# 06_-_MEMORY.net
KiCad netlist of a schematic drawn in Altium Designer
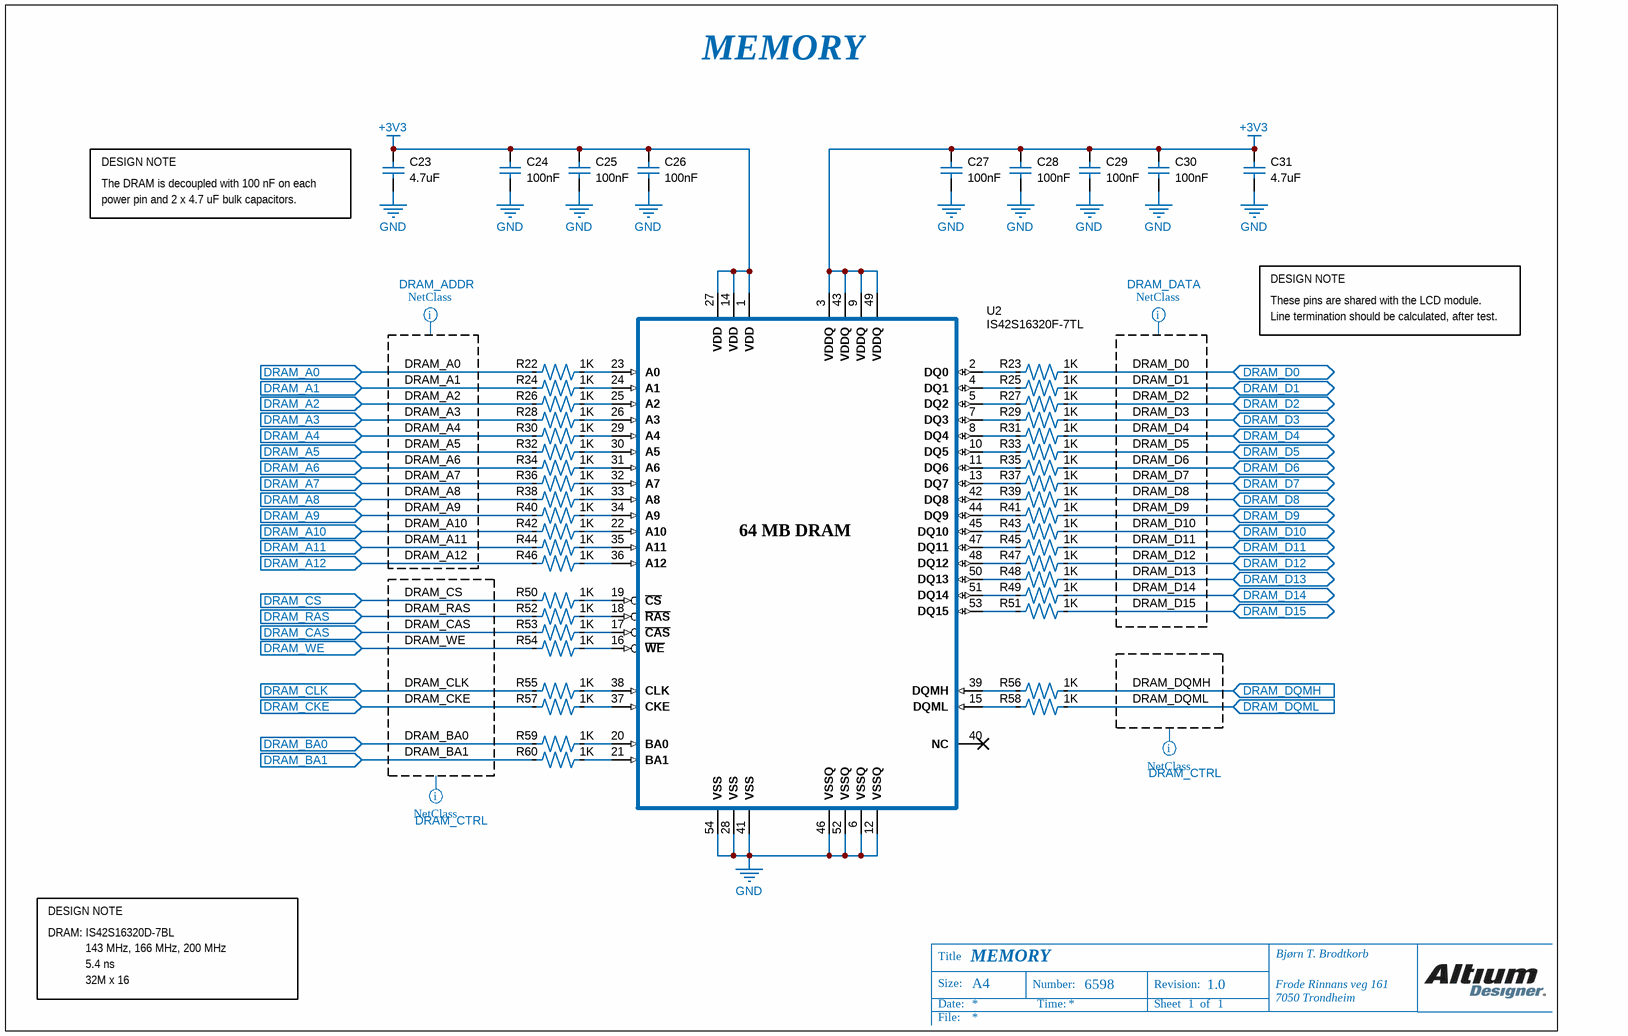
[diagram p0: [06] - MEMORY.SchDoc]

(export (version "E")
  (design (tool "Eeschema 10.0.6"))
  (components
    (comp (ref "C23")
      (value "4.7uF")
      (footprint "C0603")
      (description "C0603")
      (fields (field (name "Comment") "02016D104KAT2A"))
      (libsource (lib "Passive components") (part "02016D104KAT2A"))
    )
    (comp (ref "C24")
      (value "100nF")
      (footprint "C0402")
      (description "C0402")
      (fields (field (name "Comment") "04023C103KAT2A"))
      (libsource (lib "Passive components") (part "04023C103KAT2A"))
    )
    (comp (ref "C25")
      (value "100nF")
      (footprint "C0402")
      (description "C0402")
      (fields (field (name "Comment") "04023C103KAT2A"))
      (libsource (lib "Passive components") (part "04023C103KAT2A"))
    )
    (comp (ref "C26")
      (value "100nF")
      (footprint "C0402")
      (description "C0402")
      (fields (field (name "Comment") "04023C103KAT2A"))
      (libsource (lib "Passive components") (part "04023C103KAT2A"))
    )
    (comp (ref "C27")
      (value "100nF")
      (footprint "C0402")
      (description "C0402")
      (fields (field (name "Comment") "04023C103KAT2A"))
      (libsource (lib "Passive components") (part "04023C103KAT2A"))
    )
    (comp (ref "C28")
      (value "100nF")
      (footprint "C0402")
      (description "C0402")
      (fields (field (name "Comment") "04023C103KAT2A"))
      (libsource (lib "Passive components") (part "04023C103KAT2A"))
    )
    (comp (ref "C29")
      (value "100nF")
      (footprint "C0402")
      (description "C0402")
      (fields (field (name "Comment") "04023C103KAT2A"))
      (libsource (lib "Passive components") (part "04023C103KAT2A"))
    )
    (comp (ref "C30")
      (value "100nF")
      (footprint "C0402")
      (description "C0402")
      (fields (field (name "Comment") "04023C103KAT2A"))
      (libsource (lib "Passive components") (part "04023C103KAT2A"))
    )
    (comp (ref "C31")
      (value "4.7uF")
      (footprint "C0603")
      (description "C0603")
      (fields (field (name "Comment") "02016D104KAT2A"))
      (libsource (lib "Passive components") (part "02016D104KAT2A"))
    )
    (comp (ref "R22")
      (value "1K")
      (footprint "R0402")
      (description "R0402")
      (fields (field (name "Comment") "CRCW04020000Z0ED"))
      (libsource (lib "Passive components") (part "CRCW04020000Z0ED"))
    )
    (comp (ref "R23")
      (value "1K")
      (footprint "R0402")
      (description "R0402")
      (fields (field (name "Comment") "CRCW04020000Z0ED"))
      (libsource (lib "Passive components") (part "CRCW04020000Z0ED"))
    )
    (comp (ref "R24")
      (value "1K")
      (footprint "R0402")
      (description "R0402")
      (fields (field (name "Comment") "CRCW04020000Z0ED"))
      (libsource (lib "Passive components") (part "CRCW04020000Z0ED"))
    )
    (comp (ref "R25")
      (value "1K")
      (footprint "R0402")
      (description "R0402")
      (fields (field (name "Comment") "CRCW04020000Z0ED"))
      (libsource (lib "Passive components") (part "CRCW04020000Z0ED"))
    )
    (comp (ref "R26")
      (value "1K")
      (footprint "R0402")
      (description "R0402")
      (fields (field (name "Comment") "CRCW04020000Z0ED"))
      (libsource (lib "Passive components") (part "CRCW04020000Z0ED"))
    )
    (comp (ref "R27")
      (value "1K")
      (footprint "R0402")
      (description "R0402")
      (fields (field (name "Comment") "CRCW04020000Z0ED"))
      (libsource (lib "Passive components") (part "CRCW04020000Z0ED"))
    )
    (comp (ref "R28")
      (value "1K")
      (footprint "R0402")
      (description "R0402")
      (fields (field (name "Comment") "CRCW04020000Z0ED"))
      (libsource (lib "Passive components") (part "CRCW04020000Z0ED"))
    )
    (comp (ref "R29")
      (value "1K")
      (footprint "R0402")
      (description "R0402")
      (fields (field (name "Comment") "CRCW04020000Z0ED"))
      (libsource (lib "Passive components") (part "CRCW04020000Z0ED"))
    )
    (comp (ref "R30")
      (value "1K")
      (footprint "R0402")
      (description "R0402")
      (fields (field (name "Comment") "CRCW04020000Z0ED"))
      (libsource (lib "Passive components") (part "CRCW04020000Z0ED"))
    )
    (comp (ref "R31")
      (value "1K")
      (footprint "R0402")
      (description "R0402")
      (fields (field (name "Comment") "CRCW04020000Z0ED"))
      (libsource (lib "Passive components") (part "CRCW04020000Z0ED"))
    )
    (comp (ref "R32")
      (value "1K")
      (footprint "R0402")
      (description "R0402")
      (fields (field (name "Comment") "CRCW04020000Z0ED"))
      (libsource (lib "Passive components") (part "CRCW04020000Z0ED"))
    )
    (comp (ref "R33")
      (value "1K")
      (footprint "R0402")
      (description "R0402")
      (fields (field (name "Comment") "CRCW04020000Z0ED"))
      (libsource (lib "Passive components") (part "CRCW04020000Z0ED"))
    )
    (comp (ref "R34")
      (value "1K")
      (footprint "R0402")
      (description "R0402")
      (fields (field (name "Comment") "CRCW04020000Z0ED"))
      (libsource (lib "Passive components") (part "CRCW04020000Z0ED"))
    )
    (comp (ref "R35")
      (value "1K")
      (footprint "R0402")
      (description "R0402")
      (fields (field (name "Comment") "CRCW04020000Z0ED"))
      (libsource (lib "Passive components") (part "CRCW04020000Z0ED"))
    )
    (comp (ref "R36")
      (value "1K")
      (footprint "R0402")
      (description "R0402")
      (fields (field (name "Comment") "CRCW04020000Z0ED"))
      (libsource (lib "Passive components") (part "CRCW04020000Z0ED"))
    )
    (comp (ref "R37")
      (value "1K")
      (footprint "R0402")
      (description "R0402")
      (fields (field (name "Comment") "CRCW04020000Z0ED"))
      (libsource (lib "Passive components") (part "CRCW04020000Z0ED"))
    )
    (comp (ref "R38")
      (value "1K")
      (footprint "R0402")
      (description "R0402")
      (fields (field (name "Comment") "CRCW04020000Z0ED"))
      (libsource (lib "Passive components") (part "CRCW04020000Z0ED"))
    )
    (comp (ref "R39")
      (value "1K")
      (footprint "R0402")
      (description "R0402")
      (fields (field (name "Comment") "CRCW04020000Z0ED"))
      (libsource (lib "Passive components") (part "CRCW04020000Z0ED"))
    )
    (comp (ref "R40")
      (value "1K")
      (footprint "R0402")
      (description "R0402")
      (fields (field (name "Comment") "CRCW04020000Z0ED"))
      (libsource (lib "Passive components") (part "CRCW04020000Z0ED"))
    )
    (comp (ref "R41")
      (value "1K")
      (footprint "R0402")
      (description "R0402")
      (fields (field (name "Comment") "CRCW04020000Z0ED"))
      (libsource (lib "Passive components") (part "CRCW04020000Z0ED"))
    )
    (comp (ref "R42")
      (value "1K")
      (footprint "R0402")
      (description "R0402")
      (fields (field (name "Comment") "CRCW04020000Z0ED"))
      (libsource (lib "Passive components") (part "CRCW04020000Z0ED"))
    )
    (comp (ref "R43")
      (value "1K")
      (footprint "R0402")
      (description "R0402")
      (fields (field (name "Comment") "CRCW04020000Z0ED"))
      (libsource (lib "Passive components") (part "CRCW04020000Z0ED"))
    )
    (comp (ref "R44")
      (value "1K")
      (footprint "R0402")
      (description "R0402")
      (fields (field (name "Comment") "CRCW04020000Z0ED"))
      (libsource (lib "Passive components") (part "CRCW04020000Z0ED"))
    )
    (comp (ref "R45")
      (value "1K")
      (footprint "R0402")
      (description "R0402")
      (fields (field (name "Comment") "CRCW04020000Z0ED"))
      (libsource (lib "Passive components") (part "CRCW04020000Z0ED"))
    )
    (comp (ref "R46")
      (value "1K")
      (footprint "R0402")
      (description "R0402")
      (fields (field (name "Comment") "CRCW04020000Z0ED"))
      (libsource (lib "Passive components") (part "CRCW04020000Z0ED"))
    )
    (comp (ref "R47")
      (value "1K")
      (footprint "R0402")
      (description "R0402")
      (fields (field (name "Comment") "CRCW04020000Z0ED"))
      (libsource (lib "Passive components") (part "CRCW04020000Z0ED"))
    )
    (comp (ref "R48")
      (value "1K")
      (footprint "R0402")
      (description "R0402")
      (fields (field (name "Comment") "CRCW04020000Z0ED"))
      (libsource (lib "Passive components") (part "CRCW04020000Z0ED"))
    )
    (comp (ref "R49")
      (value "1K")
      (footprint "R0402")
      (description "R0402")
      (fields (field (name "Comment") "CRCW04020000Z0ED"))
      (libsource (lib "Passive components") (part "CRCW04020000Z0ED"))
    )
    (comp (ref "R50")
      (value "1K")
      (footprint "R0402")
      (description "R0402")
      (fields (field (name "Comment") "CRCW04020000Z0ED"))
      (libsource (lib "Passive components") (part "CRCW04020000Z0ED"))
    )
    (comp (ref "R51")
      (value "1K")
      (footprint "R0402")
      (description "R0402")
      (fields (field (name "Comment") "CRCW04020000Z0ED"))
      (libsource (lib "Passive components") (part "CRCW04020000Z0ED"))
    )
    (comp (ref "R52")
      (value "1K")
      (footprint "R0402")
      (description "R0402")
      (fields (field (name "Comment") "CRCW04020000Z0ED"))
      (libsource (lib "Passive components") (part "CRCW04020000Z0ED"))
    )
    (comp (ref "R53")
      (value "1K")
      (footprint "R0402")
      (description "R0402")
      (fields (field (name "Comment") "CRCW04020000Z0ED"))
      (libsource (lib "Passive components") (part "CRCW04020000Z0ED"))
    )
    (comp (ref "R54")
      (value "1K")
      (footprint "R0402")
      (description "R0402")
      (fields (field (name "Comment") "CRCW04020000Z0ED"))
      (libsource (lib "Passive components") (part "CRCW04020000Z0ED"))
    )
    (comp (ref "R55")
      (value "1K")
      (footprint "R0402")
      (description "R0402")
      (fields (field (name "Comment") "CRCW04020000Z0ED"))
      (libsource (lib "Passive components") (part "CRCW04020000Z0ED"))
    )
    (comp (ref "R56")
      (value "1K")
      (footprint "R0402")
      (description "R0402")
      (fields (field (name "Comment") "CRCW04020000Z0ED"))
      (libsource (lib "Passive components") (part "CRCW04020000Z0ED"))
    )
    (comp (ref "R57")
      (value "1K")
      (footprint "R0402")
      (description "R0402")
      (fields (field (name "Comment") "CRCW04020000Z0ED"))
      (libsource (lib "Passive components") (part "CRCW04020000Z0ED"))
    )
    (comp (ref "R58")
      (value "1K")
      (footprint "R0402")
      (description "R0402")
      (fields (field (name "Comment") "CRCW04020000Z0ED"))
      (libsource (lib "Passive components") (part "CRCW04020000Z0ED"))
    )
    (comp (ref "R59")
      (value "1K")
      (footprint "R0402")
      (description "R0402")
      (fields (field (name "Comment") "CRCW04020000Z0ED"))
      (libsource (lib "Passive components") (part "CRCW04020000Z0ED"))
    )
    (comp (ref "R60")
      (value "1K")
      (footprint "R0402")
      (description "R0402")
      (fields (field (name "Comment") "CRCW04020000Z0ED"))
      (libsource (lib "Passive components") (part "CRCW04020000Z0ED"))
    )
    (comp (ref "U2")
      (value "IS42S16320F-7TL")
      (footprint "IS42S16320F-7TL")
      (description "SDRAM 512Mb 32Mx16 TSOP")
      (libsource (lib "Memory") (part "IS42S16320F-7TL"))
    )
  )
  (nets
    (net (code "1") (name "+3V3") (class "Default")
      (node (ref "C23") (pin "2") (pinfunction "2_2") (pintype "passive"))
      (node (ref "C24") (pin "2") (pinfunction "2_2") (pintype "passive"))
      (node (ref "C25") (pin "2") (pinfunction "2_2") (pintype "passive"))
      (node (ref "C26") (pin "2") (pinfunction "2_2") (pintype "passive"))
      (node (ref "C27") (pin "2") (pinfunction "2_2") (pintype "passive"))
      (node (ref "C28") (pin "2") (pinfunction "2_2") (pintype "passive"))
      (node (ref "C29") (pin "2") (pinfunction "2_2") (pintype "passive"))
      (node (ref "C30") (pin "2") (pinfunction "2_2") (pintype "passive"))
      (node (ref "C31") (pin "2") (pinfunction "2_2") (pintype "passive"))
      (node (ref "U2") (pin "1") (pinfunction "VDD_1") (pintype "power_in"))
      (node (ref "U2") (pin "14") (pinfunction "VDD_14") (pintype "power_in"))
      (node (ref "U2") (pin "27") (pinfunction "VDD_27") (pintype "power_in"))
      (node (ref "U2") (pin "3") (pinfunction "VDDQ_3") (pintype "power_in"))
      (node (ref "U2") (pin "43") (pinfunction "VDDQ_43") (pintype "power_in"))
      (node (ref "U2") (pin "49") (pinfunction "VDDQ_49") (pintype "power_in"))
      (node (ref "U2") (pin "9") (pinfunction "VDDQ_9") (pintype "power_in"))
    )
    (net (code "2") (name "/DRAM_A0") (class "Default")
      (node (ref "R22") (pin "1") (pinfunction "1_1") (pintype "passive"))
    )
    (net (code "3") (name "/DRAM_A1") (class "Default")
      (node (ref "R24") (pin "1") (pinfunction "1_1") (pintype "passive"))
    )
    (net (code "4") (name "/DRAM_A2") (class "Default")
      (node (ref "R26") (pin "1") (pinfunction "1_1") (pintype "passive"))
    )
    (net (code "5") (name "/DRAM_A3") (class "Default")
      (node (ref "R28") (pin "1") (pinfunction "1_1") (pintype "passive"))
    )
    (net (code "6") (name "/DRAM_A4") (class "Default")
      (node (ref "R30") (pin "1") (pinfunction "1_1") (pintype "passive"))
    )
    (net (code "7") (name "/DRAM_A5") (class "Default")
      (node (ref "R32") (pin "1") (pinfunction "1_1") (pintype "passive"))
    )
    (net (code "8") (name "/DRAM_A6") (class "Default")
      (node (ref "R34") (pin "1") (pinfunction "1_1") (pintype "passive"))
    )
    (net (code "9") (name "/DRAM_A7") (class "Default")
      (node (ref "R36") (pin "1") (pinfunction "1_1") (pintype "passive"))
    )
    (net (code "10") (name "/DRAM_A8") (class "Default")
      (node (ref "R38") (pin "1") (pinfunction "1_1") (pintype "passive"))
    )
    (net (code "11") (name "/DRAM_A9") (class "Default")
      (node (ref "R40") (pin "1") (pinfunction "1_1") (pintype "passive"))
    )
    (net (code "12") (name "/DRAM_A10") (class "Default")
      (node (ref "R42") (pin "1") (pinfunction "1_1") (pintype "passive"))
    )
    (net (code "13") (name "/DRAM_A11") (class "Default")
      (node (ref "R44") (pin "1") (pinfunction "1_1") (pintype "passive"))
    )
    (net (code "14") (name "/DRAM_A12") (class "Default")
      (node (ref "R46") (pin "1") (pinfunction "1_1") (pintype "passive"))
    )
    (net (code "15") (name "/DRAM_BA0") (class "Default")
      (node (ref "R59") (pin "1") (pinfunction "1_1") (pintype "passive"))
    )
    (net (code "16") (name "/DRAM_BA1") (class "Default")
      (node (ref "R60") (pin "1") (pinfunction "1_1") (pintype "passive"))
    )
    (net (code "17") (name "/DRAM_CAS") (class "Default")
      (node (ref "R53") (pin "1") (pinfunction "1_1") (pintype "passive"))
    )
    (net (code "18") (name "/DRAM_CKE") (class "Default")
      (node (ref "R57") (pin "1") (pinfunction "1_1") (pintype "passive"))
    )
    (net (code "19") (name "/DRAM_CLK") (class "Default")
      (node (ref "R55") (pin "1") (pinfunction "1_1") (pintype "passive"))
    )
    (net (code "20") (name "/DRAM_CS") (class "Default")
      (node (ref "R50") (pin "1") (pinfunction "1_1") (pintype "passive"))
    )
    (net (code "21") (name "/DRAM_D0") (class "Default")
      (node (ref "R23") (pin "2") (pinfunction "3_2") (pintype "passive"))
    )
    (net (code "22") (name "/DRAM_D1") (class "Default")
      (node (ref "R25") (pin "2") (pinfunction "3_2") (pintype "passive"))
    )
    (net (code "23") (name "/DRAM_D2") (class "Default")
      (node (ref "R27") (pin "2") (pinfunction "3_2") (pintype "passive"))
    )
    (net (code "24") (name "/DRAM_D3") (class "Default")
      (node (ref "R29") (pin "2") (pinfunction "3_2") (pintype "passive"))
    )
    (net (code "25") (name "/DRAM_D4") (class "Default")
      (node (ref "R31") (pin "2") (pinfunction "3_2") (pintype "passive"))
    )
    (net (code "26") (name "/DRAM_D5") (class "Default")
      (node (ref "R33") (pin "2") (pinfunction "3_2") (pintype "passive"))
    )
    (net (code "27") (name "/DRAM_D6") (class "Default")
      (node (ref "R35") (pin "2") (pinfunction "3_2") (pintype "passive"))
    )
    (net (code "28") (name "/DRAM_D7") (class "Default")
      (node (ref "R37") (pin "2") (pinfunction "3_2") (pintype "passive"))
    )
    (net (code "29") (name "/DRAM_D8") (class "Default")
      (node (ref "R39") (pin "2") (pinfunction "3_2") (pintype "passive"))
    )
    (net (code "30") (name "/DRAM_D9") (class "Default")
      (node (ref "R41") (pin "2") (pinfunction "3_2") (pintype "passive"))
    )
    (net (code "31") (name "/DRAM_D10") (class "Default")
      (node (ref "R43") (pin "2") (pinfunction "3_2") (pintype "passive"))
    )
    (net (code "32") (name "/DRAM_D11") (class "Default")
      (node (ref "R45") (pin "2") (pinfunction "3_2") (pintype "passive"))
    )
    (net (code "33") (name "/DRAM_D12") (class "Default")
      (node (ref "R47") (pin "2") (pinfunction "3_2") (pintype "passive"))
    )
    (net (code "34") (name "/DRAM_D13") (class "Default")
      (node (ref "R48") (pin "2") (pinfunction "3_2") (pintype "passive"))
    )
    (net (code "35") (name "/DRAM_D14") (class "Default")
      (node (ref "R49") (pin "2") (pinfunction "3_2") (pintype "passive"))
    )
    (net (code "36") (name "/DRAM_D15") (class "Default")
      (node (ref "R51") (pin "2") (pinfunction "3_2") (pintype "passive"))
    )
    (net (code "37") (name "/DRAM_DQMH") (class "Default")
      (node (ref "R56") (pin "2") (pinfunction "3_2") (pintype "passive"))
    )
    (net (code "38") (name "/DRAM_DQML") (class "Default")
      (node (ref "R58") (pin "2") (pinfunction "3_2") (pintype "passive"))
    )
    (net (code "39") (name "/DRAM_RAS") (class "Default")
      (node (ref "R52") (pin "1") (pinfunction "1_1") (pintype "passive"))
    )
    (net (code "40") (name "/DRAM_WE") (class "Default")
      (node (ref "R54") (pin "1") (pinfunction "1_1") (pintype "passive"))
    )
    (net (code "41") (name "GND") (class "Default")
      (node (ref "C23") (pin "1") (pinfunction "1_1") (pintype "passive"))
      (node (ref "C24") (pin "1") (pinfunction "1_1") (pintype "passive"))
      (node (ref "C25") (pin "1") (pinfunction "1_1") (pintype "passive"))
      (node (ref "C26") (pin "1") (pinfunction "1_1") (pintype "passive"))
      (node (ref "C27") (pin "1") (pinfunction "1_1") (pintype "passive"))
      (node (ref "C28") (pin "1") (pinfunction "1_1") (pintype "passive"))
      (node (ref "C29") (pin "1") (pinfunction "1_1") (pintype "passive"))
      (node (ref "C30") (pin "1") (pinfunction "1_1") (pintype "passive"))
      (node (ref "C31") (pin "1") (pinfunction "1_1") (pintype "passive"))
      (node (ref "U2") (pin "12") (pinfunction "VSSQ_12") (pintype "power_in"))
      (node (ref "U2") (pin "28") (pinfunction "VSS_28") (pintype "power_in"))
      (node (ref "U2") (pin "41") (pinfunction "VSS_41") (pintype "power_in"))
      (node (ref "U2") (pin "46") (pinfunction "VSSQ_46") (pintype "power_in"))
      (node (ref "U2") (pin "52") (pinfunction "VSSQ_52") (pintype "power_in"))
      (node (ref "U2") (pin "54") (pinfunction "VSS_54") (pintype "power_in"))
      (node (ref "U2") (pin "6") (pinfunction "VSSQ_6") (pintype "power_in"))
    )
    (net (code "42") (name "Net-(R22-3)") (class "Default")
      (node (ref "R22") (pin "2") (pinfunction "3_2") (pintype "passive"))
      (node (ref "U2") (pin "23") (pinfunction "A0_23") (pintype "input"))
    )
    (net (code "43") (name "Net-(R24-3)") (class "Default")
      (node (ref "R24") (pin "2") (pinfunction "3_2") (pintype "passive"))
      (node (ref "U2") (pin "24") (pinfunction "A1_24") (pintype "input"))
    )
    (net (code "44") (name "Net-(R26-3)") (class "Default")
      (node (ref "R26") (pin "2") (pinfunction "3_2") (pintype "passive"))
      (node (ref "U2") (pin "25") (pinfunction "A2_25") (pintype "input"))
    )
    (net (code "45") (name "Net-(R28-3)") (class "Default")
      (node (ref "R28") (pin "2") (pinfunction "3_2") (pintype "passive"))
      (node (ref "U2") (pin "26") (pinfunction "A3_26") (pintype "input"))
    )
    (net (code "46") (name "Net-(R30-3)") (class "Default")
      (node (ref "R30") (pin "2") (pinfunction "3_2") (pintype "passive"))
      (node (ref "U2") (pin "29") (pinfunction "A4_29") (pintype "input"))
    )
    (net (code "47") (name "Net-(R32-3)") (class "Default")
      (node (ref "R32") (pin "2") (pinfunction "3_2") (pintype "passive"))
      (node (ref "U2") (pin "30") (pinfunction "A5_30") (pintype "input"))
    )
    (net (code "48") (name "Net-(R34-3)") (class "Default")
      (node (ref "R34") (pin "2") (pinfunction "3_2") (pintype "passive"))
      (node (ref "U2") (pin "31") (pinfunction "A6_31") (pintype "input"))
    )
    (net (code "49") (name "Net-(R36-3)") (class "Default")
      (node (ref "R36") (pin "2") (pinfunction "3_2") (pintype "passive"))
      (node (ref "U2") (pin "32") (pinfunction "A7_32") (pintype "input"))
    )
    (net (code "50") (name "Net-(R38-3)") (class "Default")
      (node (ref "R38") (pin "2") (pinfunction "3_2") (pintype "passive"))
      (node (ref "U2") (pin "33") (pinfunction "A8_33") (pintype "input"))
    )
    (net (code "51") (name "Net-(R40-3)") (class "Default")
      (node (ref "R40") (pin "2") (pinfunction "3_2") (pintype "passive"))
      (node (ref "U2") (pin "34") (pinfunction "A9_34") (pintype "input"))
    )
    (net (code "52") (name "Net-(R42-3)") (class "Default")
      (node (ref "R42") (pin "2") (pinfunction "3_2") (pintype "passive"))
      (node (ref "U2") (pin "22") (pinfunction "A10_22") (pintype "input"))
    )
    (net (code "53") (name "Net-(R44-3)") (class "Default")
      (node (ref "R44") (pin "2") (pinfunction "3_2") (pintype "passive"))
      (node (ref "U2") (pin "35") (pinfunction "A11_35") (pintype "input"))
    )
    (net (code "54") (name "Net-(R46-3)") (class "Default")
      (node (ref "R46") (pin "2") (pinfunction "3_2") (pintype "passive"))
      (node (ref "U2") (pin "36") (pinfunction "A12_36") (pintype "input"))
    )
    (net (code "55") (name "Net-(R50-3)") (class "Default")
      (node (ref "R50") (pin "2") (pinfunction "3_2") (pintype "passive"))
      (node (ref "U2") (pin "19") (pinfunction "~{CS}_19") (pintype "input"))
    )
    (net (code "56") (name "Net-(R52-3)") (class "Default")
      (node (ref "R52") (pin "2") (pinfunction "3_2") (pintype "passive"))
      (node (ref "U2") (pin "18") (pinfunction "~{RAS}_18") (pintype "input"))
    )
    (net (code "57") (name "Net-(R53-3)") (class "Default")
      (node (ref "R53") (pin "2") (pinfunction "3_2") (pintype "passive"))
      (node (ref "U2") (pin "17") (pinfunction "~{CAS}_17") (pintype "input"))
    )
    (net (code "58") (name "Net-(R54-3)") (class "Default")
      (node (ref "R54") (pin "2") (pinfunction "3_2") (pintype "passive"))
      (node (ref "U2") (pin "16") (pinfunction "~{WE}_16") (pintype "input"))
    )
    (net (code "59") (name "Net-(R55-3)") (class "Default")
      (node (ref "R55") (pin "2") (pinfunction "3_2") (pintype "passive"))
      (node (ref "U2") (pin "38") (pinfunction "CLK_38") (pintype "input"))
    )
    (net (code "60") (name "Net-(R57-3)") (class "Default")
      (node (ref "R57") (pin "2") (pinfunction "3_2") (pintype "passive"))
      (node (ref "U2") (pin "37") (pinfunction "CKE_37") (pintype "input"))
    )
    (net (code "61") (name "Net-(R59-3)") (class "Default")
      (node (ref "R59") (pin "2") (pinfunction "3_2") (pintype "passive"))
      (node (ref "U2") (pin "20") (pinfunction "BA0_20") (pintype "input"))
    )
    (net (code "62") (name "Net-(R60-3)") (class "Default")
      (node (ref "R60") (pin "2") (pinfunction "3_2") (pintype "passive"))
      (node (ref "U2") (pin "21") (pinfunction "BA1_21") (pintype "input"))
    )
    (net (code "63") (name "Net-(U2-DQ0)") (class "Default")
      (node (ref "R23") (pin "1") (pinfunction "1_1") (pintype "passive"))
      (node (ref "U2") (pin "2") (pinfunction "DQ0_2") (pintype "bidirectional"))
    )
    (net (code "64") (name "Net-(U2-DQ1)") (class "Default")
      (node (ref "R25") (pin "1") (pinfunction "1_1") (pintype "passive"))
      (node (ref "U2") (pin "4") (pinfunction "DQ1_4") (pintype "bidirectional"))
    )
    (net (code "65") (name "Net-(U2-DQ2)") (class "Default")
      (node (ref "R27") (pin "1") (pinfunction "1_1") (pintype "passive"))
      (node (ref "U2") (pin "5") (pinfunction "DQ2_5") (pintype "bidirectional"))
    )
    (net (code "66") (name "Net-(U2-DQ3)") (class "Default")
      (node (ref "R29") (pin "1") (pinfunction "1_1") (pintype "passive"))
      (node (ref "U2") (pin "7") (pinfunction "DQ3_7") (pintype "bidirectional"))
    )
    (net (code "67") (name "Net-(U2-DQ4)") (class "Default")
      (node (ref "R31") (pin "1") (pinfunction "1_1") (pintype "passive"))
      (node (ref "U2") (pin "8") (pinfunction "DQ4_8") (pintype "bidirectional"))
    )
    (net (code "68") (name "Net-(U2-DQ5)") (class "Default")
      (node (ref "R33") (pin "1") (pinfunction "1_1") (pintype "passive"))
      (node (ref "U2") (pin "10") (pinfunction "DQ5_10") (pintype "bidirectional"))
    )
    (net (code "69") (name "Net-(U2-DQ6)") (class "Default")
      (node (ref "R35") (pin "1") (pinfunction "1_1") (pintype "passive"))
      (node (ref "U2") (pin "11") (pinfunction "DQ6_11") (pintype "bidirectional"))
    )
    (net (code "70") (name "Net-(U2-DQ7)") (class "Default")
      (node (ref "R37") (pin "1") (pinfunction "1_1") (pintype "passive"))
      (node (ref "U2") (pin "13") (pinfunction "DQ7_13") (pintype "bidirectional"))
    )
    (net (code "71") (name "Net-(U2-DQ8)") (class "Default")
      (node (ref "R39") (pin "1") (pinfunction "1_1") (pintype "passive"))
      (node (ref "U2") (pin "42") (pinfunction "DQ8_42") (pintype "bidirectional"))
    )
    (net (code "72") (name "Net-(U2-DQ9)") (class "Default")
      (node (ref "R41") (pin "1") (pinfunction "1_1") (pintype "passive"))
      (node (ref "U2") (pin "44") (pinfunction "DQ9_44") (pintype "bidirectional"))
    )
    (net (code "73") (name "Net-(U2-DQ10)") (class "Default")
      (node (ref "R43") (pin "1") (pinfunction "1_1") (pintype "passive"))
      (node (ref "U2") (pin "45") (pinfunction "DQ10_45") (pintype "bidirectional"))
    )
    (net (code "74") (name "Net-(U2-DQ11)") (class "Default")
      (node (ref "R45") (pin "1") (pinfunction "1_1") (pintype "passive"))
      (node (ref "U2") (pin "47") (pinfunction "DQ11_47") (pintype "bidirectional"))
    )
    (net (code "75") (name "Net-(U2-DQ12)") (class "Default")
      (node (ref "R47") (pin "1") (pinfunction "1_1") (pintype "passive"))
      (node (ref "U2") (pin "48") (pinfunction "DQ12_48") (pintype "bidirectional"))
    )
    (net (code "76") (name "Net-(U2-DQ13)") (class "Default")
      (node (ref "R48") (pin "1") (pinfunction "1_1") (pintype "passive"))
      (node (ref "U2") (pin "50") (pinfunction "DQ13_50") (pintype "bidirectional"))
    )
    (net (code "77") (name "Net-(U2-DQ14)") (class "Default")
      (node (ref "R49") (pin "1") (pinfunction "1_1") (pintype "passive"))
      (node (ref "U2") (pin "51") (pinfunction "DQ14_51") (pintype "bidirectional"))
    )
    (net (code "78") (name "Net-(U2-DQ15)") (class "Default")
      (node (ref "R51") (pin "1") (pinfunction "1_1") (pintype "passive"))
      (node (ref "U2") (pin "53") (pinfunction "DQ15_53") (pintype "bidirectional"))
    )
    (net (code "79") (name "Net-(U2-DQMH)") (class "Default")
      (node (ref "R56") (pin "1") (pinfunction "1_1") (pintype "passive"))
      (node (ref "U2") (pin "39") (pinfunction "DQMH_39") (pintype "input"))
    )
    (net (code "80") (name "Net-(U2-DQML)") (class "Default")
      (node (ref "R58") (pin "1") (pinfunction "1_1") (pintype "passive"))
      (node (ref "U2") (pin "15") (pinfunction "DQML_15") (pintype "input"))
    )
    (net (code "81") (name "unconnected-(U2-NC-Pad40)") (class "Default")
      (node (ref "U2") (pin "40") (pinfunction "NC_40") (pintype "passive+no_connect"))
    )
  )
)
